# BEE_BOARD_POWER.net
KiCad netlist of a schematic drawn in Altium Designer
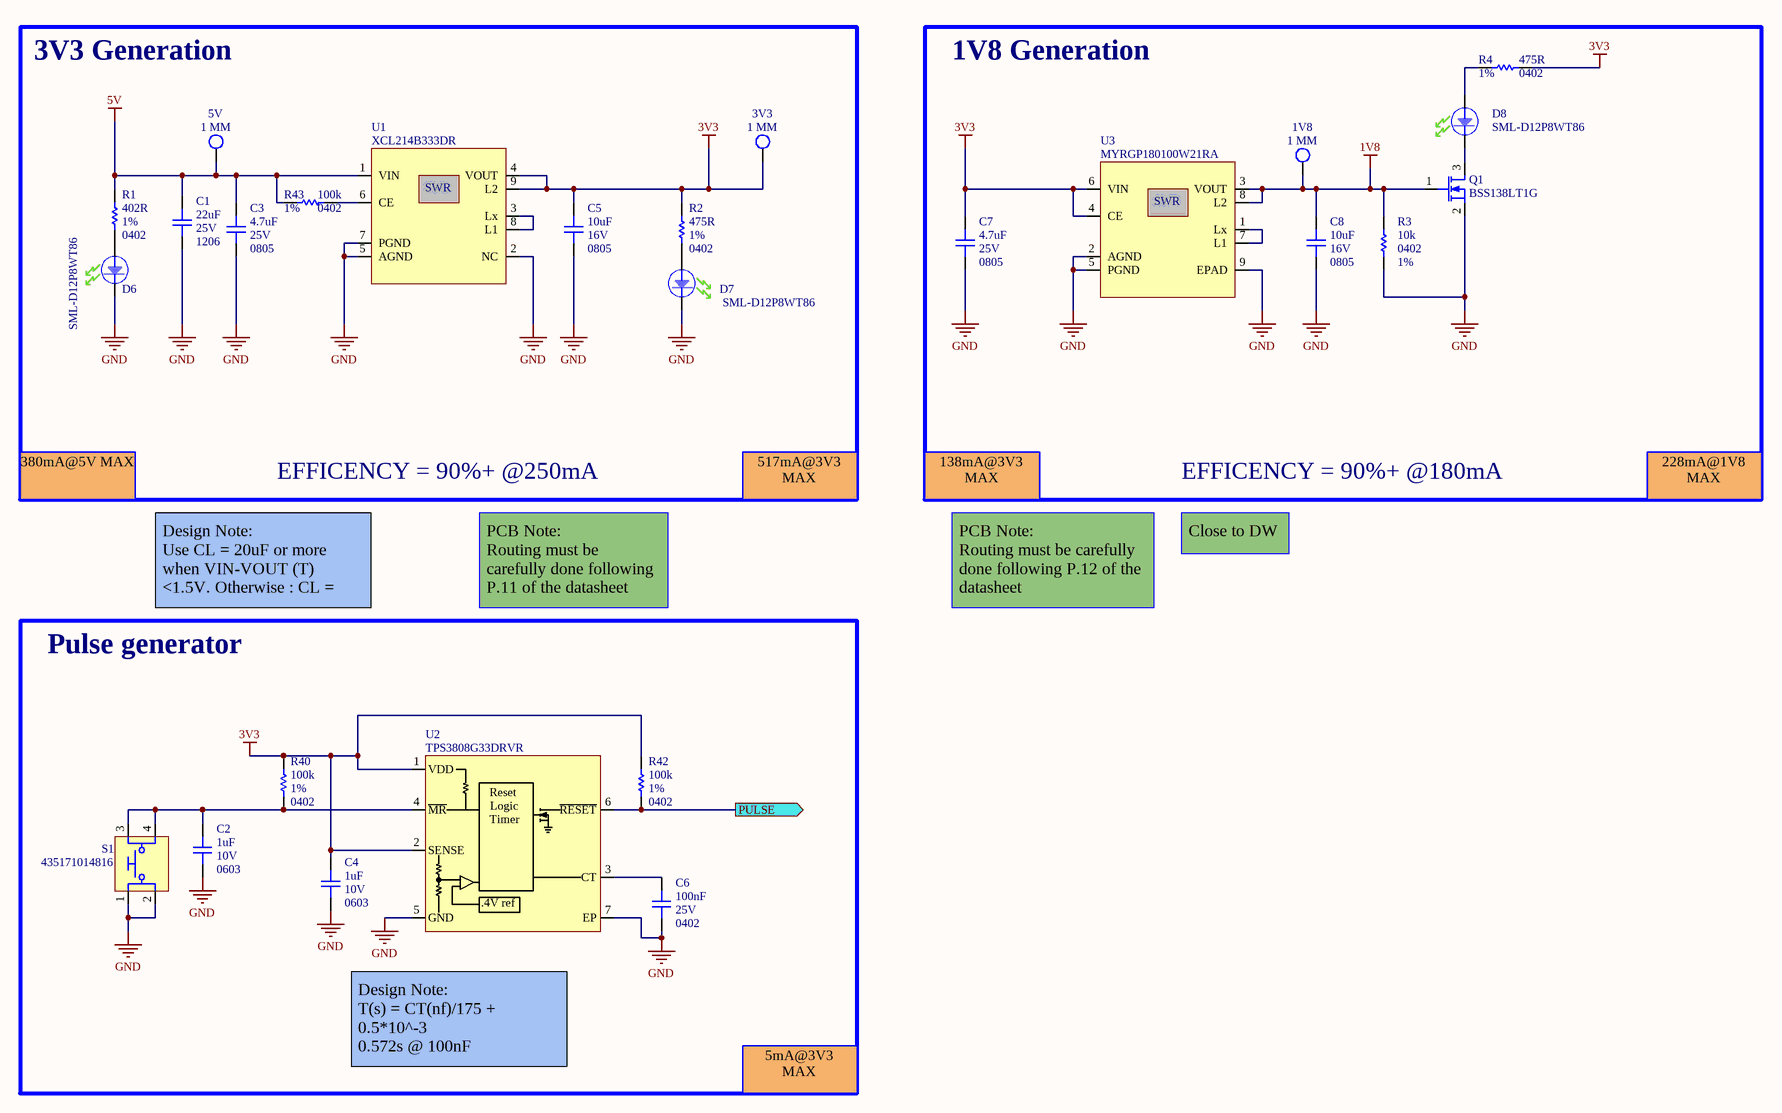
[diagram p0: BEE_BOARD_POWER.SchDoc]

(export (version "E")
  (design (tool "Eeschema 10.0.6"))
  (components
    (comp (ref "1V8")
      (value "1 MM")
      (footprint "GRAMS_MASTER_LIB_PCB:TPO_SMD_ROUND_1MM")
      (description "TPO - TEST POINT ROUND SMD PAD ONLY  - 1 MM")
      (fields
        (field (name "CREATEDBY/DATE") "Jonathan Bouchard 2018-07-17")
        (field (name "VERIFIEDBY") "Arnaud Samson 23-07-18")
      )
      (libsource (lib "GRAMS_MASTER_LIB_SCH") (part "TPO_SMD_ROUND_1MM"))
    )
    (comp (ref "3V3")
      (value "1 MM")
      (footprint "GRAMS_MASTER_LIB_PCB:TPO_SMD_ROUND_1MM")
      (description "TPO - TEST POINT ROUND SMD PAD ONLY  - 1 MM")
      (fields
        (field (name "CREATEDBY/DATE") "Jonathan Bouchard 2018-07-17")
        (field (name "VERIFIEDBY") "Arnaud Samson 23-07-18")
      )
      (libsource (lib "GRAMS_MASTER_LIB_SCH") (part "TPO_SMD_ROUND_1MM"))
    )
    (comp (ref "5V")
      (value "1 MM")
      (footprint "GRAMS_MASTER_LIB_PCB:TPO_SMD_ROUND_1MM")
      (description "TPO - TEST POINT ROUND SMD PAD ONLY  - 1 MM")
      (fields
        (field (name "CREATEDBY/DATE") "Jonathan Bouchard 2018-07-17")
        (field (name "VERIFIEDBY") "Arnaud Samson 23-07-18")
      )
      (libsource (lib "GRAMS_MASTER_LIB_SCH") (part "TPO_SMD_ROUND_1MM"))
    )
    (comp (ref "C1")
      (value "22uF")
      (footprint "grams_master_lib_pcb:CAP_CER_1206")
      (description "CAP - CER 22uF 10% 25V X5R - 1206")
      (fields
        (field (name "TOLERANCE") "10%")
        (field (name "PACKAGE") "1206")
        (field (name "VOLTAGE RATING") "25V")
        (field (name "Comment") "CL31A226KAHNNNE")
        (field (name "CREATEDBY/DATE") "Philippe Arsenault/21 Janvier 2020")
        (field (name "VERIFIEDBY") "C.Paulin - 28/01/2020")
      )
      (libsource (lib "GRAMS_MASTER_LIB_SCH") (part "CAP_CER_CL31A226KAHNNNE"))
    )
    (comp (ref "C2")
      (value "1uF")
      (footprint "CAP_CER_0603")
      (description "CAP - CER 1uF 10V 10% X5R - 0603")
      (fields
        (field (name "TOLERANCE") "10%")
        (field (name "PACKAGE") "0603")
        (field (name "VOLTAGE RATING") "10V")
        (field (name "Comment") "C0603C105K8PACTU")
        (field (name "CREATEDBY/DATE") "Hubert Dube - 21/07/20")
        (field (name "VERIFIEDBY") "Louis-Daniel Gaulin - 21/07/20")
      )
      (libsource (lib "SWARMUS_LIB") (part "CAP_CER_C0603C105K8PACTU"))
    )
    (comp (ref "C3")
      (value "4.7uF")
      (footprint "GRAMS_MASTER_LIB_PCB:CAP_CER_0805")
      (description "CAP - CER 4.7UF 10% 25V X7R - 0805")
      (fields
        (field (name "TOLERANCE") "10%")
        (field (name "PACKAGE") "0805")
        (field (name "VOLTAGE RATING") "25V")
        (field (name "Comment") "C2012X7R1E475K125AE")
        (field (name "CREATEDBY/DATE") "Keven Deslandes - 2018/11/09")
        (field (name "VERIFIEDBY") "Nicolas Roy - 2018/12/11")
      )
      (libsource (lib "GRAMS_MASTER_LIB_SCH") (part "CAP_CER_C2012X7R1E475K125AE"))
    )
    (comp (ref "C4")
      (value "1uF")
      (footprint "CAP_CER_0603")
      (description "CAP - CER 1uF 10V 10% X5R - 0603")
      (fields
        (field (name "TOLERANCE") "10%")
        (field (name "PACKAGE") "0603")
        (field (name "VOLTAGE RATING") "10V")
        (field (name "Comment") "C0603C105K8PACTU")
        (field (name "CREATEDBY/DATE") "Hubert Dube - 21/07/20")
        (field (name "VERIFIEDBY") "Louis-Daniel Gaulin - 21/07/20")
      )
      (libsource (lib "SWARMUS_LIB") (part "CAP_CER_C0603C105K8PACTU"))
    )
    (comp (ref "C5")
      (value "10uF")
      (footprint "GRAMS_MASTER_LIB_PCB:CAP_CER_0805")
      (description "CAP - CER 10UF 10% 16V X5R - 0805")
      (fields
        (field (name "TOLERANCE") "10%")
        (field (name "PACKAGE") "0805")
        (field (name "VOLTAGE RATING") "16V")
        (field (name "Comment") "GRM21BR61C106KE15K")
        (field (name "CREATEDBY/DATE") "Caroline Paulin / 8 août 2018")
        (field (name "VERIFIEDBY") "Nicolas V. (2019-01-22)")
      )
      (libsource (lib "GRAMS_MASTER_LIB_SCH") (part "CAP_CER_GRM21BR61C106KE15K"))
    )
    (comp (ref "C6")
      (value "100nF")
      (footprint "GRAMS_MASTER_LIB_PCB:CAP_CER_0402")
      (description "CAP - CER 0.1µF 10% 25V X7R - 0402")
      (fields
        (field (name "TOLERANCE") "10%")
        (field (name "PACKAGE") "0402")
        (field (name "VOLTAGE RATING") "25V")
        (field (name "Comment") "CGA2B3X7R1E104K050BB")
        (field (name "CREATEDBY/DATE") "Nicolas Roy 2018-11-07")
        (field (name "VERIFIEDBY") "Nicolas V. (2019-01-22)")
      )
      (libsource (lib "GRAMS_MASTER_LIB_SCH") (part "CAP_CER_CGA2B3X7R1E104K050BB"))
    )
    (comp (ref "C7")
      (value "4.7uF")
      (footprint "GRAMS_MASTER_LIB_PCB:CAP_CER_0805")
      (description "CAP - CER 4.7UF 10% 25V X7R - 0805")
      (fields
        (field (name "TOLERANCE") "10%")
        (field (name "PACKAGE") "0805")
        (field (name "VOLTAGE RATING") "25V")
        (field (name "Comment") "C2012X7R1E475K125AE")
        (field (name "CREATEDBY/DATE") "Keven Deslandes - 2018/11/09")
        (field (name "VERIFIEDBY") "Nicolas Roy - 2018/12/11")
      )
      (libsource (lib "GRAMS_MASTER_LIB_SCH") (part "CAP_CER_C2012X7R1E475K125AE"))
    )
    (comp (ref "C8")
      (value "10uF")
      (footprint "GRAMS_MASTER_LIB_PCB:CAP_CER_0805")
      (description "CAP - CER 10UF 10% 16V X5R - 0805")
      (fields
        (field (name "TOLERANCE") "10%")
        (field (name "PACKAGE") "0805")
        (field (name "VOLTAGE RATING") "16V")
        (field (name "Comment") "GRM21BR61C106KE15K")
        (field (name "CREATEDBY/DATE") "Caroline Paulin / 8 août 2018")
        (field (name "VERIFIEDBY") "Nicolas V. (2019-01-22)")
      )
      (libsource (lib "GRAMS_MASTER_LIB_SCH") (part "CAP_CER_GRM21BR61C106KE15K"))
    )
    (comp (ref "D6")
      (value "SML-D12P8WT86")
      (footprint "GRAMS_MASTER_LIB_PCB:LED_SML-D12P8WT86")
      (description "LED - GREEN DIFFUSED 0603 SMD - 0603")
      (fields
        (field (name "CREATEDBY/DATE") "Keven Deslandes - 2018/11/21")
        (field (name "VERIFIEDBY") "Caroline Paulin - 13 février 2019")
      )
      (libsource (lib "GRAMS_MASTER_LIB_SCH") (part "LED_SML-D12P8WT86"))
    )
    (comp (ref "D7")
      (value "SML-D12P8WT86")
      (footprint "GRAMS_MASTER_LIB_PCB:LED_SML-D12P8WT86")
      (description "LED - GREEN DIFFUSED 0603 SMD - 0603")
      (fields
        (field (name "CREATEDBY/DATE") "Keven Deslandes - 2018/11/21")
        (field (name "VERIFIEDBY") "Caroline Paulin - 13 février 2019")
      )
      (libsource (lib "GRAMS_MASTER_LIB_SCH") (part "LED_SML-D12P8WT86"))
    )
    (comp (ref "D8")
      (value "SML-D12P8WT86")
      (footprint "GRAMS_MASTER_LIB_PCB:LED_SML-D12P8WT86")
      (description "LED - GREEN DIFFUSED 0603 SMD - 0603")
      (fields
        (field (name "CREATEDBY/DATE") "Keven Deslandes - 2018/11/21")
        (field (name "VERIFIEDBY") "Caroline Paulin - 13 février 2019")
      )
      (libsource (lib "GRAMS_MASTER_LIB_SCH") (part "LED_SML-D12P8WT86"))
    )
    (comp (ref "Q1")
      (value "BSS138LT1G")
      (footprint "GRAMS_MASTER_LIB_PCB:TRX_NMOS_BSS138LT1G")
      (description "TRX - NMOS - 50V 200MA - SOT−23-3")
      (fields
        (field (name "CREATEDBY/DATE") "Joel Lemay 2018-06-15")
        (field (name "VERIFIEDBY") "Caroline Paulin - 6 sept 2018")
      )
      (libsource (lib "GRAMS_MASTER_LIB_SCH") (part "TRX_NMOS_BSS138LT1G"))
    )
    (comp (ref "R1")
      (value "402R")
      (footprint "GRAMS_MASTER_LIB_PCB:RES_0402")
      (description "RES - 402R 1% 1/10W - 0402")
      (fields
        (field (name "TOLERANCE") "1%")
        (field (name "PACKAGE") "0402")
        (field (name "Comment") "ERJ-2RKF4020X")
        (field (name "CREATEDBY/DATE") "Keven Deslandes 2018-09-20")
        (field (name "VERIFIEDBY") "Caroline Paulin - 18/12/2018")
      )
      (libsource (lib "GRAMS_MASTER_LIB_SCH") (part "RES_ERJ-2RKF4020X"))
    )
    (comp (ref "R2")
      (value "475R")
      (footprint "GRAMS_MASTER_LIB_PCB:RES_0402")
      (description "RES - 475R 1% 1/10W- 0402")
      (fields
        (field (name "TOLERANCE") "1%")
        (field (name "PACKAGE") "0402")
        (field (name "Comment") "ERJ-2RKF4750X")
        (field (name "CREATEDBY/DATE") "Keven Deslandes 2018-10-17")
        (field (name "VERIFIEDBY") "Carolilne Paulin - 18/12/2018")
      )
      (libsource (lib "GRAMS_MASTER_LIB_SCH") (part "RES_ERJ-2RKF4750X"))
    )
    (comp (ref "R3")
      (value "10k")
      (footprint "GRAMS_MASTER_LIB_PCB:RES_0402")
      (description "RES - 10K OHMS 1% 1/16W - 0402")
      (fields
        (field (name "TOLERANCE") "1%")
        (field (name "PACKAGE") "0402")
        (field (name "Comment") "RC0402FR-0710KL")
        (field (name "CREATEDBY/DATE") "Nicolas V. (2018-11-20)")
        (field (name "VERIFIEDBY") "Nicolas V. (2018-11-20)")
      )
      (libsource (lib "GRAMS_MASTER_LIB_SCH") (part "RES_RC0402FR-0710KL"))
    )
    (comp (ref "R4")
      (value "475R")
      (footprint "GRAMS_MASTER_LIB_PCB:RES_0402")
      (description "RES - 475R 1% 1/10W- 0402")
      (fields
        (field (name "TOLERANCE") "1%")
        (field (name "PACKAGE") "0402")
        (field (name "Comment") "ERJ-2RKF4750X")
        (field (name "CREATEDBY/DATE") "Keven Deslandes 2018-10-17")
        (field (name "VERIFIEDBY") "Carolilne Paulin - 18/12/2018")
      )
      (libsource (lib "GRAMS_MASTER_LIB_SCH") (part "RES_ERJ-2RKF4750X"))
    )
    (comp (ref "R40")
      (value "100k")
      (footprint "GRAMS_MASTER_LIB_PCB:RES_0402")
      (description "RES - 100K 1% 1/16W - 0402")
      (fields
        (field (name "TOLERANCE") "1%")
        (field (name "PACKAGE") "0402")
        (field (name "Comment") "RC0402FR-07100KL")
        (field (name "CREATEDBY/DATE") "Keven Deslandes 2018-10-19")
        (field (name "VERIFIEDBY") "Caroline Paulin - 18/12/2018")
      )
      (libsource (lib "GRAMS_MASTER_LIB_SCH") (part "RES_RC0402FR-07100KL"))
    )
    (comp (ref "R42")
      (value "100k")
      (footprint "GRAMS_MASTER_LIB_PCB:RES_0402")
      (description "RES - 100K 1% 1/16W - 0402")
      (fields
        (field (name "TOLERANCE") "1%")
        (field (name "PACKAGE") "0402")
        (field (name "Comment") "RC0402FR-07100KL")
        (field (name "CREATEDBY/DATE") "Keven Deslandes 2018-10-19")
        (field (name "VERIFIEDBY") "Caroline Paulin - 18/12/2018")
      )
      (libsource (lib "GRAMS_MASTER_LIB_SCH") (part "RES_RC0402FR-07100KL"))
    )
    (comp (ref "R43")
      (value "100k")
      (footprint "GRAMS_MASTER_LIB_PCB:RES_0402")
      (description "RES - 100K 1% 1/16W - 0402")
      (fields
        (field (name "TOLERANCE") "1%")
        (field (name "PACKAGE") "0402")
        (field (name "Comment") "RC0402FR-07100KL")
        (field (name "CREATEDBY/DATE") "Keven Deslandes 2018-10-19")
        (field (name "VERIFIEDBY") "Caroline Paulin - 18/12/2018")
      )
      (libsource (lib "GRAMS_MASTER_LIB_SCH") (part "RES_RC0402FR-07100KL"))
    )
    (comp (ref "S1")
      (value "435171014816")
      (footprint "SWI_TACT_435171014816")
      (description "SWI - SWITCH TACTILE SPST-NO 0.05A 12V -SMD")
      (fields
        (field (name "CREATEDBY/DATE") "Hubert Dube - 22/07/20")
        (field (name "VERIFIEDBY") "Louis-Daniel Gaulin / 12-11-2020")
      )
      (libsource (lib "SWARMUS_LIB") (part "SWI_TACT_435171014816"))
    )
    (comp (ref "U1")
      (value "XCL214B333DR")
      (footprint "REG_SWR_XCL214B333DR")
      (description "REG_DC DC CONVERTER 3.3V 5W_9-PowerTFQFN")
      (fields
        (field (name "CREATEDBY/DATE") "Louis-Daniel Gaulin / 21-07-2020")
        (field (name "VERIFIEDBY") "Philippe Arsenault/2020-11-06")
      )
      (libsource (lib "SWARMUS_LIB") (part "REG_SWR_XCL214B333DR"))
    )
    (comp (ref "U2")
      (value "TPS3808G33DRVR")
      (footprint "POW_TPS3808G33DRVR")
      (description "POW - Programmable-Delay Supervisory Circuit Open Drain - 6WSON")
      (fields
        (field (name "CREATEDBY/DATE") "Philippe Arsenault/2021-04-19")
        (field (name "VERIFIEDBY") "Louis-Daniel Gaulin / 29-04-2021")
      )
      (libsource (lib "SWARMUS_LIB") (part "POW_TPS3808G33DRVR"))
    )
    (comp (ref "U3")
      (value "MYRGP180100W21RA")
      (footprint "REG_SWR_MYRGP180100W21RA")
      (description "REG_DC DC CONVERTER 1.8V 1.8W_8-PowerTDFN")
      (fields
        (field (name "CREATEDBY/DATE") "Louis-Daniel Gaulin / 21-07-2020")
        (field (name "VERIFIEDBY") "Philippe Arsenault/2020-11-06")
      )
      (libsource (lib "SWARMUS_LIB") (part "REG_SWR_MYRGP180100W21RA"))
    )
  )
  (nets
    (net (code "1") (name "/PULSE") (class "Default")
      (node (ref "R42") (pin "1") (pinfunction "1_1") (pintype "passive"))
      (node (ref "U2") (pin "6") (pinfunction "~{RESET}_6") (pintype "passive"))
    )
    (net (code "2") (name "1V8") (class "Default")
      (node (ref "1V8") (pin "1") (pinfunction "1_1") (pintype "passive"))
      (node (ref "C8") (pin "2") (pinfunction "2_2") (pintype "passive"))
      (node (ref "Q1") (pin "1") (pinfunction "G_1") (pintype "passive"))
      (node (ref "R3") (pin "1") (pinfunction "1_1") (pintype "passive"))
      (node (ref "U3") (pin "3") (pinfunction "VOUT_3") (pintype "passive"))
      (node (ref "U3") (pin "8") (pinfunction "L2_8") (pintype "passive"))
    )
    (net (code "3") (name "3V3") (class "Default")
      (node (ref "3V3") (pin "1") (pinfunction "1_1") (pintype "passive"))
      (node (ref "C4") (pin "1") (pinfunction "1_1") (pintype "passive"))
      (node (ref "C5") (pin "2") (pinfunction "2_2") (pintype "passive"))
      (node (ref "C7") (pin "2") (pinfunction "2_2") (pintype "passive"))
      (node (ref "R2") (pin "2") (pinfunction "2_2") (pintype "passive"))
      (node (ref "R4") (pin "1") (pinfunction "1_1") (pintype "passive"))
      (node (ref "R40") (pin "2") (pinfunction "2_2") (pintype "passive"))
      (node (ref "R42") (pin "2") (pinfunction "2_2") (pintype "passive"))
      (node (ref "U1") (pin "4") (pinfunction "VOUT_4") (pintype "passive"))
      (node (ref "U1") (pin "9") (pinfunction "L2_9") (pintype "passive"))
      (node (ref "U2") (pin "1") (pinfunction "VDD_1") (pintype "passive"))
      (node (ref "U2") (pin "2") (pinfunction "SENSE_2") (pintype "passive"))
      (node (ref "U3") (pin "4") (pinfunction "CE_4") (pintype "passive"))
      (node (ref "U3") (pin "6") (pinfunction "VIN_6") (pintype "passive"))
    )
    (net (code "4") (name "5V") (class "Default")
      (node (ref "5V") (pin "1") (pinfunction "1_1") (pintype "passive"))
      (node (ref "C1") (pin "2") (pinfunction "2_2") (pintype "passive"))
      (node (ref "C3") (pin "2") (pinfunction "2_2") (pintype "passive"))
      (node (ref "R1") (pin "2") (pinfunction "2_2") (pintype "passive"))
      (node (ref "R43") (pin "2") (pinfunction "2_2") (pintype "passive"))
      (node (ref "U1") (pin "1") (pinfunction "VIN_1") (pintype "passive"))
    )
    (net (code "5") (name "GND") (class "Default")
      (node (ref "C1") (pin "1") (pinfunction "1_1") (pintype "passive"))
      (node (ref "C2") (pin "2") (pinfunction "2_2") (pintype "passive"))
      (node (ref "C3") (pin "1") (pinfunction "1_1") (pintype "passive"))
      (node (ref "C4") (pin "2") (pinfunction "2_2") (pintype "passive"))
      (node (ref "C5") (pin "1") (pinfunction "1_1") (pintype "passive"))
      (node (ref "C6") (pin "1") (pinfunction "1_1") (pintype "passive"))
      (node (ref "C7") (pin "1") (pinfunction "1_1") (pintype "passive"))
      (node (ref "C8") (pin "1") (pinfunction "1_1") (pintype "passive"))
      (node (ref "D6") (pin "K") (pinfunction "K_K") (pintype "passive"))
      (node (ref "D7") (pin "K") (pinfunction "K_K") (pintype "passive"))
      (node (ref "Q1") (pin "2") (pinfunction "S_2") (pintype "passive"))
      (node (ref "R3") (pin "2") (pinfunction "2_2") (pintype "passive"))
      (node (ref "S1") (pin "1") (pinfunction "1_1") (pintype "passive"))
      (node (ref "S1") (pin "2") (pinfunction "2_2") (pintype "passive"))
      (node (ref "U1") (pin "2") (pinfunction "NC_2") (pintype "passive"))
      (node (ref "U1") (pin "5") (pinfunction "AGND_5") (pintype "passive"))
      (node (ref "U1") (pin "7") (pinfunction "PGND_7") (pintype "passive"))
      (node (ref "U2") (pin "5") (pinfunction "GND_5") (pintype "passive"))
      (node (ref "U2") (pin "7") (pinfunction "EP_7") (pintype "passive"))
      (node (ref "U3") (pin "2") (pinfunction "AGND_2") (pintype "passive"))
      (node (ref "U3") (pin "5") (pinfunction "PGND_5") (pintype "passive"))
      (node (ref "U3") (pin "9") (pinfunction "EPAD_9") (pintype "passive"))
    )
    (net (code "6") (name "Net-(D6-PadA)") (class "Default")
      (node (ref "D6") (pin "A") (pinfunction "A_A") (pintype "passive"))
      (node (ref "R1") (pin "1") (pinfunction "1_1") (pintype "passive"))
    )
    (net (code "7") (name "Net-(D7-PadA)") (class "Default")
      (node (ref "D7") (pin "A") (pinfunction "A_A") (pintype "passive"))
      (node (ref "R2") (pin "1") (pinfunction "1_1") (pintype "passive"))
    )
    (net (code "8") (name "Net-(D8-PadA)") (class "Default")
      (node (ref "D8") (pin "A") (pinfunction "A_A") (pintype "passive"))
      (node (ref "R4") (pin "2") (pinfunction "2_2") (pintype "passive"))
    )
    (net (code "9") (name "Net-(Q1-D)") (class "Default")
      (node (ref "D8") (pin "K") (pinfunction "K_K") (pintype "passive"))
      (node (ref "Q1") (pin "3") (pinfunction "D_3") (pintype "passive"))
    )
    (net (code "10") (name "Net-(U1-CE)") (class "Default")
      (node (ref "R43") (pin "1") (pinfunction "1_1") (pintype "passive"))
      (node (ref "U1") (pin "6") (pinfunction "CE_6") (pintype "passive"))
    )
    (net (code "11") (name "Net-(U1-L1)") (class "Default")
      (node (ref "U1") (pin "3") (pinfunction "Lx_3") (pintype "passive"))
      (node (ref "U1") (pin "8") (pinfunction "L1_8") (pintype "passive"))
    )
    (net (code "12") (name "Net-(U2-CT)") (class "Default")
      (node (ref "C6") (pin "2") (pinfunction "2_2") (pintype "passive"))
      (node (ref "U2") (pin "3") (pinfunction "CT_3") (pintype "passive"))
    )
    (net (code "13") (name "Net-(U2-~{MR})") (class "Default")
      (node (ref "C2") (pin "1") (pinfunction "1_1") (pintype "passive"))
      (node (ref "R40") (pin "1") (pinfunction "1_1") (pintype "passive"))
      (node (ref "S1") (pin "3") (pinfunction "3_3") (pintype "passive"))
      (node (ref "S1") (pin "4") (pinfunction "4_4") (pintype "passive"))
      (node (ref "U2") (pin "4") (pinfunction "~{MR}_4") (pintype "passive"))
    )
    (net (code "14") (name "Net-(U3-L1)") (class "Default")
      (node (ref "U3") (pin "1") (pinfunction "Lx_1") (pintype "passive"))
      (node (ref "U3") (pin "7") (pinfunction "L1_7") (pintype "passive"))
    )
  )
)
